# PDBueno.net
KiCad netlist of a schematic drawn in Altium Designer
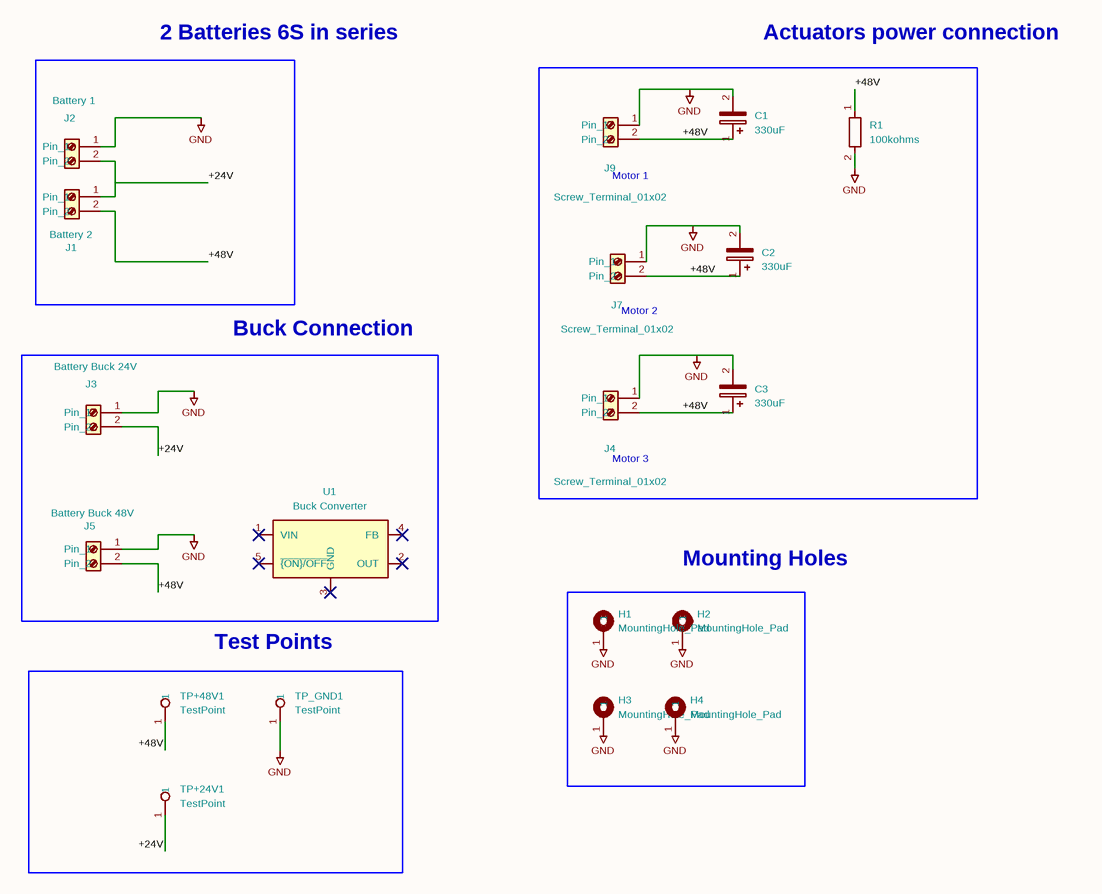
[diagram p0: PDBueno.SchDoc]

(export (version "E")
  (design (tool "Eeschema 10.0.6"))
  (components
    (comp (ref "C1")
      (value "330uF")
      (description "Polarized capacitor")
      (libsource (lib "Device") (part "C_Polarized"))
    )
    (comp (ref "C2")
      (value "330uF")
      (description "Polarized capacitor")
      (libsource (lib "Device") (part "C_Polarized"))
    )
    (comp (ref "C3")
      (value "330uF")
      (description "Polarized capacitor")
      (libsource (lib "Device") (part "C_Polarized"))
    )
    (comp (ref "H1")
      (value "MountingHole_Pad")
      (description "Mounting Hole with connection")
      (libsource (lib "Mechanical") (part "MountingHole_Pad"))
    )
    (comp (ref "H2")
      (value "MountingHole_Pad")
      (description "Mounting Hole with connection")
      (libsource (lib "Mechanical") (part "MountingHole_Pad"))
    )
    (comp (ref "H3")
      (value "MountingHole_Pad")
      (description "Mounting Hole with connection")
      (libsource (lib "Mechanical") (part "MountingHole_Pad"))
    )
    (comp (ref "H4")
      (value "MountingHole_Pad")
      (description "Mounting Hole with connection")
      (libsource (lib "Mechanical") (part "MountingHole_Pad"))
    )
    (comp (ref "J1") (value "Battery 2") (libsource (lib "Connector") (part "Screw_Terminal_01x02")))
    (comp (ref "J2") (value "Battery 1") (libsource (lib "Connector") (part "Screw_Terminal_01x02")))
    (comp (ref "J3") (value "Battery Buck 24V") (libsource (lib "Connector") (part "Screw_Terminal_01x02")))
    (comp (ref "J4")
      (value "Screw_Terminal_01x02")
      (libsource (lib "Connector") (part "Screw_Terminal_01x02"))
    )
    (comp (ref "J5") (value "Battery Buck 48V") (libsource (lib "Connector") (part "Screw_Terminal_01x02")))
    (comp (ref "J7")
      (value "Screw_Terminal_01x02")
      (libsource (lib "Connector") (part "Screw_Terminal_01x02"))
    )
    (comp (ref "J9")
      (value "Screw_Terminal_01x02")
      (libsource (lib "Connector") (part "Screw_Terminal_01x02"))
    )
    (comp (ref "R1") (value "100kohms") (description "Resistor") (libsource (lib "Device") (part "R")))
    (comp (ref "TP+24V1")
      (value "TestPoint")
      (description "test point")
      (libsource (lib "Connector") (part "TestPoint"))
    )
    (comp (ref "TP+48V1")
      (value "TestPoint")
      (description "test point")
      (libsource (lib "Connector") (part "TestPoint"))
    )
    (comp (ref "TP_GND1")
      (value "TestPoint")
      (description "test point")
      (libsource (lib "Connector") (part "TestPoint"))
    )
    (comp (ref "U1") (value "Buck Converter") (libsource (lib "Regulator_Switching") (part "LM2596S-3.3")))
  )
  (nets
    (net (code "1") (name "/+24V") (class "Default")
      (node (ref "J1") (pin "1") (pinfunction "Pin_1_1") (pintype "passive"))
      (node (ref "J2") (pin "2") (pinfunction "Pin_2_2") (pintype "passive"))
      (node (ref "J3") (pin "2") (pinfunction "Pin_2_2") (pintype "passive"))
      (node (ref "TP+24V1") (pin "1") (pinfunction "1_1") (pintype "passive"))
    )
    (net (code "2") (name "/+48V") (class "Default")
      (node (ref "C1") (pin "1") (pinfunction "1_1") (pintype "passive"))
      (node (ref "C2") (pin "1") (pinfunction "1_1") (pintype "passive"))
      (node (ref "C3") (pin "1") (pinfunction "1_1") (pintype "passive"))
      (node (ref "J1") (pin "2") (pinfunction "Pin_2_2") (pintype "passive"))
      (node (ref "J4") (pin "2") (pinfunction "Pin_2_2") (pintype "passive"))
      (node (ref "J5") (pin "2") (pinfunction "Pin_2_2") (pintype "passive"))
      (node (ref "J7") (pin "2") (pinfunction "Pin_2_2") (pintype "passive"))
      (node (ref "J9") (pin "2") (pinfunction "Pin_2_2") (pintype "passive"))
      (node (ref "R1") (pin "1") (pinfunction "1_1") (pintype "passive"))
      (node (ref "TP+48V1") (pin "1") (pinfunction "1_1") (pintype "passive"))
    )
    (net (code "3") (name "GND") (class "Default")
      (node (ref "C1") (pin "2") (pinfunction "2_2") (pintype "passive"))
      (node (ref "C2") (pin "2") (pinfunction "2_2") (pintype "passive"))
      (node (ref "C3") (pin "2") (pinfunction "2_2") (pintype "passive"))
      (node (ref "H1") (pin "1") (pinfunction "1_1") (pintype "passive"))
      (node (ref "H2") (pin "1") (pinfunction "1_1") (pintype "passive"))
      (node (ref "H3") (pin "1") (pinfunction "1_1") (pintype "passive"))
      (node (ref "H4") (pin "1") (pinfunction "1_1") (pintype "passive"))
      (node (ref "J2") (pin "1") (pinfunction "Pin_1_1") (pintype "passive"))
      (node (ref "J3") (pin "1") (pinfunction "Pin_1_1") (pintype "passive"))
      (node (ref "J4") (pin "1") (pinfunction "Pin_1_1") (pintype "passive"))
      (node (ref "J5") (pin "1") (pinfunction "Pin_1_1") (pintype "passive"))
      (node (ref "J7") (pin "1") (pinfunction "Pin_1_1") (pintype "passive"))
      (node (ref "J9") (pin "1") (pinfunction "Pin_1_1") (pintype "passive"))
      (node (ref "R1") (pin "2") (pinfunction "2_2") (pintype "passive"))
      (node (ref "TP_GND1") (pin "1") (pinfunction "1_1") (pintype "passive"))
    )
    (net (code "4") (name "unconnected-(U1-FB-Pad4)") (class "Default")
      (node (ref "U1") (pin "4") (pinfunction "FB_4") (pintype "passive+no_connect"))
    )
    (net (code "5") (name "unconnected-(U1-GND-Pad3)") (class "Default")
      (node (ref "U1") (pin "3") (pinfunction "GND_3") (pintype "passive+no_connect"))
    )
    (net (code "6") (name "unconnected-(U1-OUT-Pad2)") (class "Default")
      (node (ref "U1") (pin "2") (pinfunction "OUT_2") (pintype "passive+no_connect"))
    )
    (net (code "7") (name "unconnected-(U1-VIN-Pad1)") (class "Default")
      (node (ref "U1") (pin "1") (pinfunction "VIN_1") (pintype "passive+no_connect"))
    )
    (net (code "8") (name "unconnected-(U1-~{{ON}{slash}OFF}-Pad5)") (class "Default")
      (node (ref "U1") (pin "5") (pinfunction "~{{ON}/OFF}_5") (pintype "passive+no_connect"))
    )
  )
)
